# Analog2.net
KiCad netlist of a schematic drawn in Altium Designer
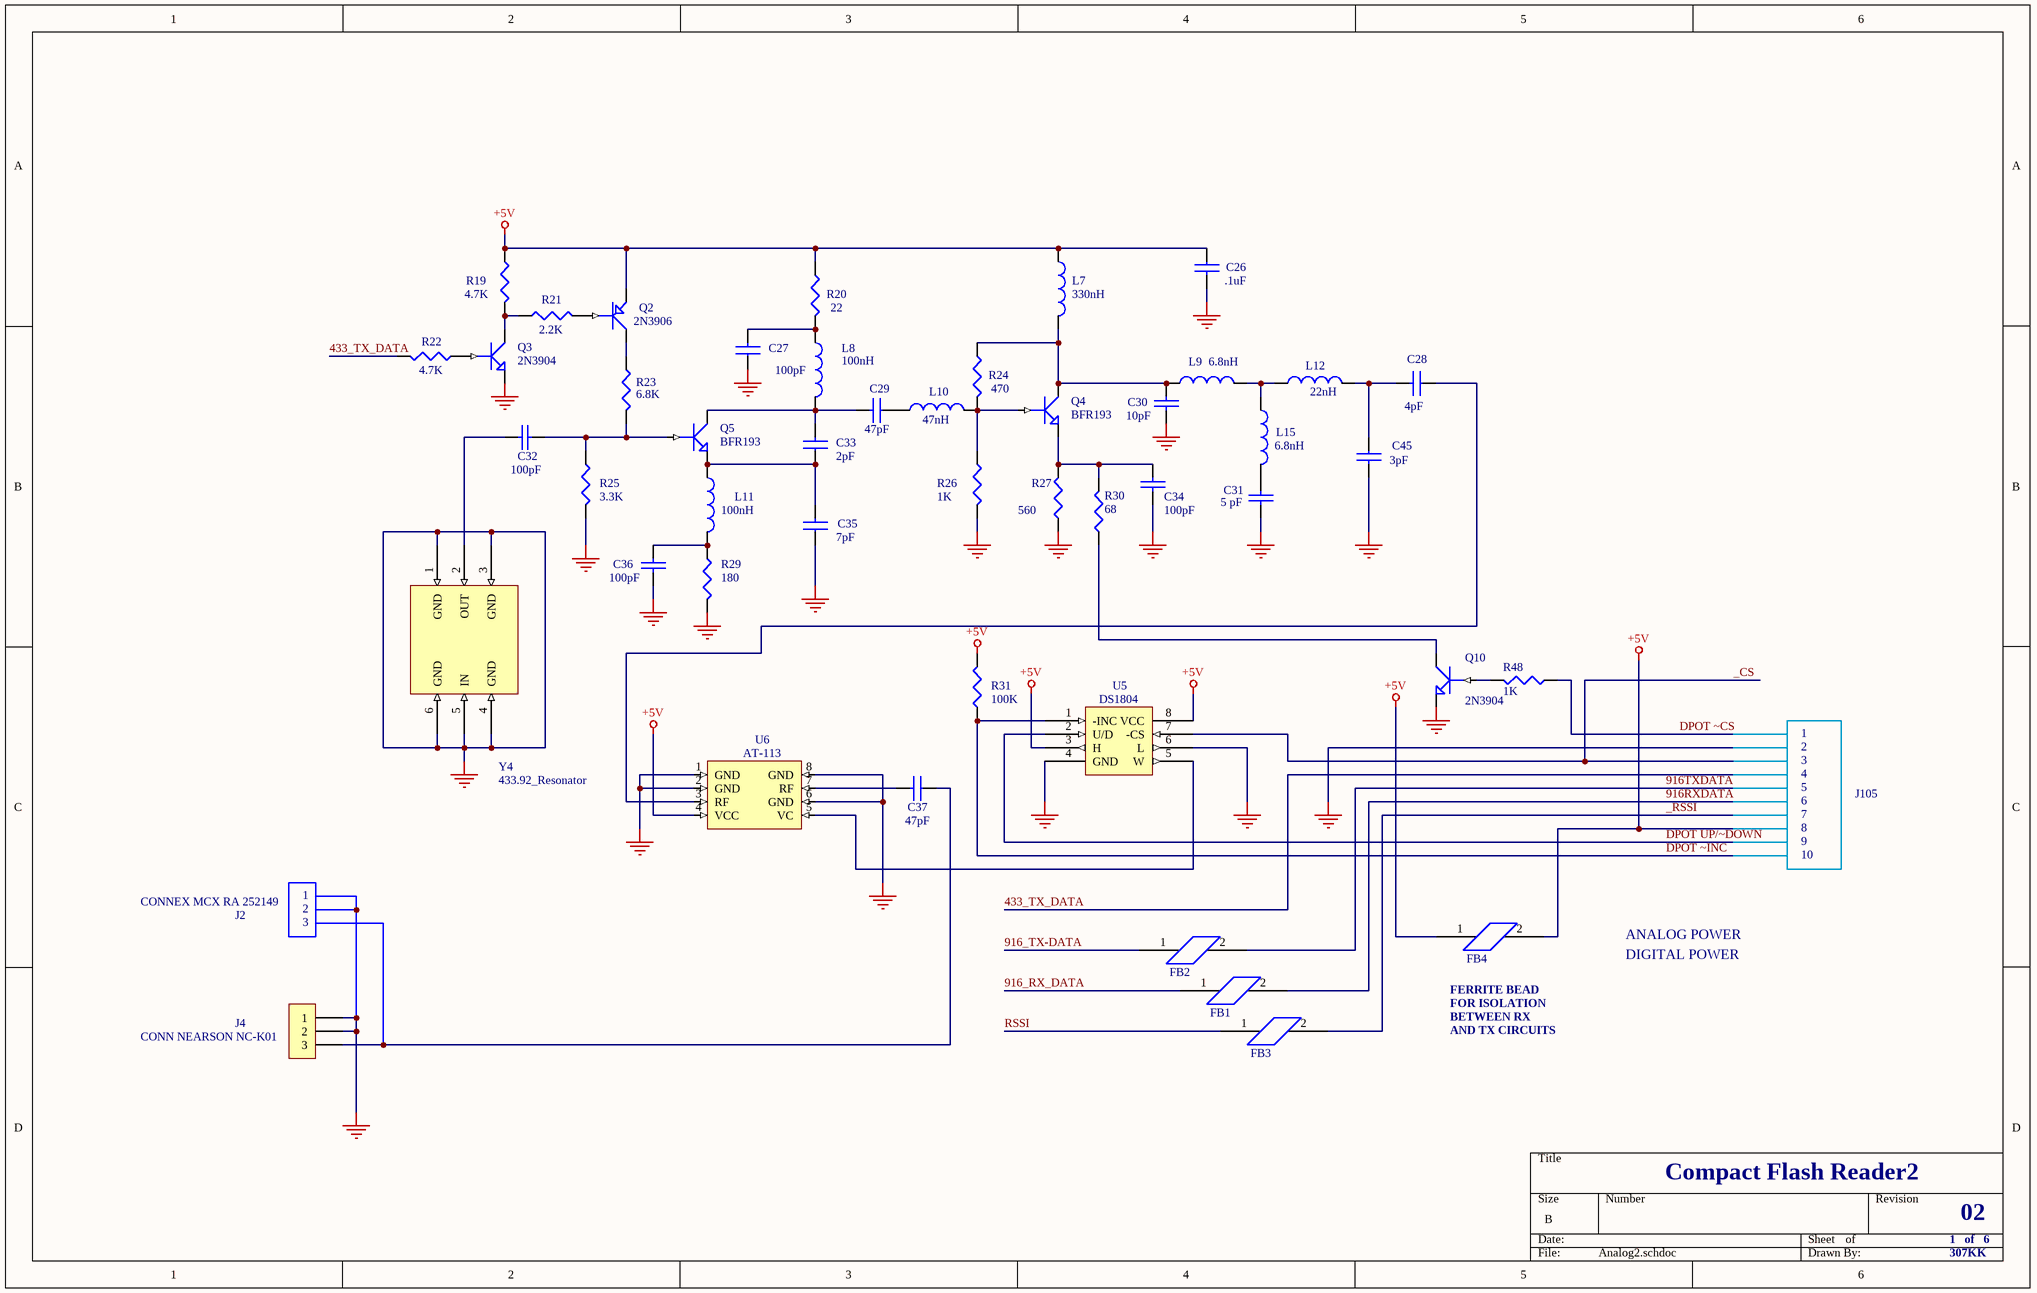
[diagram p0: Analog2.schdoc]

(export (version "E")
  (design (tool "Eeschema 10.0.6"))
  (components
    (comp (ref "C26") (value ".1uF") (footprint "0603") (libsource (lib "*") (part "CAP_NP")))
    (comp (ref "C27") (value "100pF") (footprint "0603") (libsource (lib "*") (part "CAP_NP")))
    (comp (ref "C28") (value "4pF") (footprint "0603") (libsource (lib "*") (part "CAP_NP")))
    (comp (ref "C29") (value "47pF") (footprint "0603") (libsource (lib "*") (part "CAP_NP")))
    (comp (ref "C30")
      (value "10pF")
      (footprint "0603")
      (description "Capacitor")
      (libsource (lib "*") (part "CAP"))
    )
    (comp (ref "C31")
      (value "5 pF")
      (footprint "0603")
      (description "Capacitor")
      (libsource (lib "*") (part "CAP"))
    )
    (comp (ref "C32")
      (value "100pF")
      (footprint "0603")
      (description "Capacitor")
      (libsource (lib "*") (part "CAP"))
    )
    (comp (ref "C33") (value "2pF") (footprint "0603") (libsource (lib "*") (part "CAP_NP")))
    (comp (ref "C34")
      (value "100pF")
      (footprint "0603")
      (description "Capacitor")
      (libsource (lib "*") (part "CAP"))
    )
    (comp (ref "C35") (value "7pF") (footprint "0603") (libsource (lib "*") (part "CAP_NP")))
    (comp (ref "C36")
      (value "100pF")
      (footprint "0603")
      (description "Capacitor")
      (libsource (lib "*") (part "CAP"))
    )
    (comp (ref "C37") (value "47pF") (footprint "0603") (libsource (lib "*") (part "CAP_NP")))
    (comp (ref "C45") (value "3pF") (footprint "0603") (libsource (lib "*") (part "CAP_NP")))
    (comp (ref "FB1") (value "FB") (footprint "0603") (libsource (lib "*") (part "FB_0603")))
    (comp (ref "FB2") (value "FB") (footprint "0603") (libsource (lib "*") (part "FB_0603")))
    (comp (ref "FB3") (value "FB") (footprint "0603") (libsource (lib "*") (part "FB_0603")))
    (comp (ref "FB4") (value "FB") (footprint "0603") (libsource (lib "*") (part "FB_0603")))
    (comp (ref "J4")
      (value "CONN NEARSON NC-K01")
      (footprint "CONN NEARSON NC-K01")
      (description "Connector")
      (libsource (lib "*") (part "CON3"))
    )
    (comp (ref "L7") (value "330nH") (footprint "0805") (libsource (lib "*") (part "INDUCTOR")))
    (comp (ref "L8") (value "100nH") (footprint "0603") (libsource (lib "*") (part "INDUCTOR")))
    (comp (ref "L9") (value "6.8nH") (footprint "0603") (libsource (lib "*") (part "INDUCTOR")))
    (comp (ref "L10") (value "47nH") (footprint "0603") (libsource (lib "*") (part "INDUCTOR")))
    (comp (ref "L11") (value "100nH") (footprint "0603") (libsource (lib "*") (part "INDUCTOR")))
    (comp (ref "L12") (value "22nH") (footprint "0603") (libsource (lib "*") (part "INDUCTOR")))
    (comp (ref "L15") (value "6.8nH") (footprint "0603") (libsource (lib "*") (part "INDUCTOR")))
    (comp (ref "Q2")
      (value "2N3906")
      (footprint "SOT23 TRANS")
      (description "PNP Transistor")
      (libsource (lib "*") (part "PNP1"))
    )
    (comp (ref "Q3")
      (value "2N3904")
      (footprint "SOT23 TRANS")
      (description "NPN Transistor")
      (libsource (lib "*") (part "NPN1"))
    )
    (comp (ref "Q4")
      (value "BFR193")
      (footprint "SOT23 TRANS")
      (description "NPN Transistor")
      (libsource (lib "*") (part "NPN1"))
    )
    (comp (ref "Q5")
      (value "BFR193")
      (footprint "SOT23 TRANS")
      (description "NPN Transistor")
      (libsource (lib "*") (part "NPN1"))
    )
    (comp (ref "Q10")
      (value "2N3904")
      (footprint "SOT23 TRANS")
      (description "NPN Transistor")
      (libsource (lib "*") (part "NPN1"))
    )
    (comp (ref "R19") (value "4.7K") (footprint "0603") (libsource (lib "*") (part "RESISTOR")))
    (comp (ref "R20") (value "22") (footprint "0603") (libsource (lib "*") (part "RESISTOR")))
    (comp (ref "R21") (value "2.2K") (footprint "0603") (libsource (lib "*") (part "RESISTOR")))
    (comp (ref "R22") (value "4.7K") (footprint "0603") (libsource (lib "*") (part "RESISTOR")))
    (comp (ref "R23") (value "6.8K") (footprint "0603") (libsource (lib "*") (part "RESISTOR")))
    (comp (ref "R24") (value "470") (footprint "0603") (libsource (lib "*") (part "RESISTOR")))
    (comp (ref "R25") (value "3.3K") (footprint "0603") (libsource (lib "*") (part "RESISTOR")))
    (comp (ref "R26") (value "1K") (footprint "0603") (libsource (lib "*") (part "RESISTOR")))
    (comp (ref "R27") (value "560") (footprint "0603") (libsource (lib "*") (part "RESISTOR")))
    (comp (ref "R29") (value "180") (footprint "0603") (libsource (lib "*") (part "RESISTOR")))
    (comp (ref "R30") (value "68") (footprint "0603") (libsource (lib "*") (part "RESISTOR")))
    (comp (ref "R31") (value "100K") (footprint "0603") (libsource (lib "*") (part "RESISTOR")))
    (comp (ref "R48") (value "1K") (footprint "0603") (libsource (lib "*") (part "RESISTOR")))
    (comp (ref "U5") (value "DS1804") (footprint "SO8 SMALL") (libsource (lib "*") (part "DS1804")))
    (comp (ref "U6") (value "AT-113") (footprint "SO8") (libsource (lib "*") (part "AT-113A")))
    (comp (ref "Y4")
      (value "433.92_Resonator")
      (libsource (lib "Compact Flash Reader1_1") (part "RESONATOR3"))
    )
  )
  (nets
    (net (code "1") (name "+5V") (class "Default")
      (node (ref "C26") (pin "1") (pinfunction "1_1") (pintype "passive"))
      (node (ref "FB4") (pin "1") (pinfunction "2_1") (pintype "passive"))
      (node (ref "FB4") (pin "2") (pinfunction "1_2") (pintype "passive"))
      (node (ref "L7") (pin "1") (pinfunction "1_1") (pintype "passive"))
      (node (ref "Q2") (pin "E") (pinfunction "E_E") (pintype "passive"))
      (node (ref "R19") (pin "1") (pinfunction "1_1") (pintype "passive"))
      (node (ref "R20") (pin "1") (pinfunction "1_1") (pintype "passive"))
      (node (ref "R31") (pin "1") (pinfunction "1_1") (pintype "passive"))
      (node (ref "U5") (pin "3") (pinfunction "H_3") (pintype "output"))
      (node (ref "U5") (pin "8") (pinfunction "VCC_8") (pintype "power_in"))
      (node (ref "U6") (pin "4") (pinfunction "VCC_4") (pintype "input"))
    )
    (net (code "2") (name "/433_TX_DATA") (class "Default")
      (node (ref "R22") (pin "2") (pinfunction "2_2") (pintype "passive"))
    )
    (net (code "3") (name "/916RXDATA") (class "Default")
      (node (ref "FB1") (pin "2") (pinfunction "1_2") (pintype "passive"))
    )
    (net (code "4") (name "/916TXDATA") (class "Default")
      (node (ref "FB2") (pin "2") (pinfunction "1_2") (pintype "passive"))
    )
    (net (code "5") (name "/916_RX_DATA") (class "Default")
      (node (ref "FB1") (pin "1") (pinfunction "2_1") (pintype "passive"))
    )
    (net (code "6") (name "/916_TX-DATA") (class "Default")
      (node (ref "FB2") (pin "1") (pinfunction "2_1") (pintype "passive"))
    )
    (net (code "7") (name "/DPOT UP{slash}~DOWN") (class "Default")
      (node (ref "U5") (pin "2") (pinfunction "U/D_2") (pintype "input"))
    )
    (net (code "8") (name "/DPOT ~CS") (class "Default")
      (node (ref "R48") (pin "2") (pinfunction "2_2") (pintype "passive"))
    )
    (net (code "9") (name "/DPOT ~INC") (class "Default")
      (node (ref "R31") (pin "2") (pinfunction "2_2") (pintype "passive"))
      (node (ref "U5") (pin "1") (pinfunction "-INC_1") (pintype "input"))
    )
    (net (code "10") (name "/RSSI") (class "Default")
      (node (ref "FB3") (pin "1") (pinfunction "2_1") (pintype "passive"))
    )
    (net (code "11") (name "/_CS") (class "Default")
      (node (ref "U5") (pin "7") (pinfunction "-CS_7") (pintype "input"))
    )
    (net (code "12") (name "/_RSSI") (class "Default")
      (node (ref "FB3") (pin "2") (pinfunction "1_2") (pintype "passive"))
    )
    (net (code "13") (name "GND_SIGNAL") (class "Default")
      (node (ref "C26") (pin "2") (pinfunction "2_2") (pintype "passive"))
      (node (ref "C27") (pin "1") (pinfunction "1_1") (pintype "passive"))
      (node (ref "C30") (pin "2") (pinfunction "2_2") (pintype "passive"))
      (node (ref "C31") (pin "2") (pinfunction "2_2") (pintype "passive"))
      (node (ref "C34") (pin "2") (pinfunction "2_2") (pintype "passive"))
      (node (ref "C35") (pin "1") (pinfunction "1_1") (pintype "passive"))
      (node (ref "C36") (pin "2") (pinfunction "2_2") (pintype "passive"))
      (node (ref "C45") (pin "2") (pinfunction "2_2") (pintype "passive"))
      (node (ref "J4") (pin "1") (pinfunction "1_1") (pintype "passive"))
      (node (ref "J4") (pin "2") (pinfunction "2_2") (pintype "passive"))
      (node (ref "Q10") (pin "E") (pinfunction "E_E") (pintype "passive"))
      (node (ref "Q3") (pin "E") (pinfunction "E_E") (pintype "passive"))
      (node (ref "R25") (pin "2") (pinfunction "2_2") (pintype "passive"))
      (node (ref "R26") (pin "2") (pinfunction "2_2") (pintype "passive"))
      (node (ref "R27") (pin "2") (pinfunction "2_2") (pintype "passive"))
      (node (ref "R29") (pin "2") (pinfunction "2_2") (pintype "passive"))
      (node (ref "U5") (pin "4") (pinfunction "GND_4") (pintype "power_in"))
      (node (ref "U5") (pin "6") (pinfunction "L_6") (pintype "output"))
      (node (ref "U6") (pin "1") (pinfunction "GND_1") (pintype "input"))
      (node (ref "U6") (pin "2") (pinfunction "GND_2") (pintype "input"))
      (node (ref "U6") (pin "6") (pinfunction "GND_6") (pintype "input"))
      (node (ref "U6") (pin "8") (pinfunction "GND_8") (pintype "input"))
      (node (ref "Y4") (pin "1") (pinfunction "GND_1") (pintype "input"))
      (node (ref "Y4") (pin "3") (pinfunction "GND_3") (pintype "input"))
      (node (ref "Y4") (pin "4") (pinfunction "GND_4") (pintype "input"))
      (node (ref "Y4") (pin "5") (pinfunction "IN_5") (pintype "input"))
      (node (ref "Y4") (pin "6") (pinfunction "GND_6") (pintype "input"))
    )
    (net (code "14") (name "Net-(C27-Pad2)") (class "Default")
      (node (ref "C27") (pin "2") (pinfunction "2_2") (pintype "passive"))
      (node (ref "L8") (pin "1") (pinfunction "1_1") (pintype "passive"))
      (node (ref "R20") (pin "2") (pinfunction "2_2") (pintype "passive"))
    )
    (net (code "15") (name "Net-(C28-Pad1)") (class "Default")
      (node (ref "C28") (pin "1") (pinfunction "1_1") (pintype "passive"))
      (node (ref "U6") (pin "3") (pinfunction "RF_3") (pintype "input"))
    )
    (net (code "16") (name "Net-(C28-Pad2)") (class "Default")
      (node (ref "C28") (pin "2") (pinfunction "2_2") (pintype "passive"))
      (node (ref "C45") (pin "1") (pinfunction "1_1") (pintype "passive"))
      (node (ref "L12") (pin "2") (pinfunction "2_2") (pintype "passive"))
    )
    (net (code "17") (name "Net-(C29-Pad1)") (class "Default")
      (node (ref "C29") (pin "1") (pinfunction "1_1") (pintype "passive"))
      (node (ref "L10") (pin "1") (pinfunction "1_1") (pintype "passive"))
    )
    (net (code "18") (name "Net-(C29-Pad2)") (class "Default")
      (node (ref "C29") (pin "2") (pinfunction "2_2") (pintype "passive"))
      (node (ref "C33") (pin "2") (pinfunction "2_2") (pintype "passive"))
      (node (ref "L8") (pin "2") (pinfunction "2_2") (pintype "passive"))
      (node (ref "Q5") (pin "C") (pinfunction "C_C") (pintype "passive"))
    )
    (net (code "19") (name "Net-(C30-Pad1)") (class "Default")
      (node (ref "C30") (pin "1") (pinfunction "1_1") (pintype "passive"))
      (node (ref "L7") (pin "2") (pinfunction "2_2") (pintype "passive"))
      (node (ref "L9") (pin "1") (pinfunction "1_1") (pintype "passive"))
      (node (ref "Q4") (pin "C") (pinfunction "C_C") (pintype "passive"))
      (node (ref "R24") (pin "1") (pinfunction "1_1") (pintype "passive"))
    )
    (net (code "20") (name "Net-(C31-Pad1)") (class "Default")
      (node (ref "C31") (pin "1") (pinfunction "1_1") (pintype "passive"))
      (node (ref "L15") (pin "2") (pinfunction "2_2") (pintype "passive"))
    )
    (net (code "21") (name "Net-(C32-Pad2)") (class "Default")
      (node (ref "C32") (pin "2") (pinfunction "2_2") (pintype "passive"))
      (node (ref "Q5") (pin "B") (pinfunction "B_B") (pintype "input"))
      (node (ref "R23") (pin "2") (pinfunction "2_2") (pintype "passive"))
      (node (ref "R25") (pin "1") (pinfunction "1_1") (pintype "passive"))
    )
    (net (code "22") (name "Net-(C33-Pad1)") (class "Default")
      (node (ref "C33") (pin "1") (pinfunction "1_1") (pintype "passive"))
      (node (ref "C35") (pin "2") (pinfunction "2_2") (pintype "passive"))
      (node (ref "L11") (pin "1") (pinfunction "1_1") (pintype "passive"))
      (node (ref "Q5") (pin "E") (pinfunction "E_E") (pintype "passive"))
    )
    (net (code "23") (name "Net-(C34-Pad1)") (class "Default")
      (node (ref "C34") (pin "1") (pinfunction "1_1") (pintype "passive"))
      (node (ref "Q4") (pin "E") (pinfunction "E_E") (pintype "passive"))
      (node (ref "R27") (pin "1") (pinfunction "1_1") (pintype "passive"))
      (node (ref "R30") (pin "2") (pinfunction "2_2") (pintype "passive"))
    )
    (net (code "24") (name "Net-(C36-Pad1)") (class "Default")
      (node (ref "C36") (pin "1") (pinfunction "1_1") (pintype "passive"))
      (node (ref "L11") (pin "2") (pinfunction "2_2") (pintype "passive"))
      (node (ref "R29") (pin "1") (pinfunction "1_1") (pintype "passive"))
    )
    (net (code "25") (name "Net-(C37-Pad1)") (class "Default")
      (node (ref "C37") (pin "1") (pinfunction "1_1") (pintype "passive"))
      (node (ref "J4") (pin "3") (pinfunction "3_3") (pintype "passive"))
    )
    (net (code "26") (name "Net-(C37-Pad2)") (class "Default")
      (node (ref "C37") (pin "2") (pinfunction "2_2") (pintype "passive"))
      (node (ref "U6") (pin "7") (pinfunction "RF_7") (pintype "input"))
    )
    (net (code "27") (name "Net-(L10-Pad2)") (class "Default")
      (node (ref "L10") (pin "2") (pinfunction "2_2") (pintype "passive"))
      (node (ref "Q4") (pin "B") (pinfunction "B_B") (pintype "input"))
      (node (ref "R24") (pin "2") (pinfunction "2_2") (pintype "passive"))
      (node (ref "R26") (pin "1") (pinfunction "1_1") (pintype "passive"))
    )
    (net (code "28") (name "Net-(L12-Pad1)") (class "Default")
      (node (ref "L12") (pin "1") (pinfunction "1_1") (pintype "passive"))
      (node (ref "L15") (pin "1") (pinfunction "1_1") (pintype "passive"))
      (node (ref "L9") (pin "2") (pinfunction "2_2") (pintype "passive"))
    )
    (net (code "29") (name "Net-(Q2-PadB)") (class "Default")
      (node (ref "Q2") (pin "B") (pinfunction "B_B") (pintype "input"))
      (node (ref "R21") (pin "2") (pinfunction "2_2") (pintype "passive"))
    )
    (net (code "30") (name "Net-(Q2-PadC)") (class "Default")
      (node (ref "Q2") (pin "C") (pinfunction "C_C") (pintype "passive"))
      (node (ref "R23") (pin "1") (pinfunction "1_1") (pintype "passive"))
    )
    (net (code "31") (name "Net-(Q3-PadB)") (class "Default")
      (node (ref "Q3") (pin "B") (pinfunction "B_B") (pintype "input"))
      (node (ref "R22") (pin "1") (pinfunction "1_1") (pintype "passive"))
    )
    (net (code "32") (name "Net-(Q3-PadC)") (class "Default")
      (node (ref "Q3") (pin "C") (pinfunction "C_C") (pintype "passive"))
      (node (ref "R19") (pin "2") (pinfunction "2_2") (pintype "passive"))
      (node (ref "R21") (pin "1") (pinfunction "1_1") (pintype "passive"))
    )
    (net (code "33") (name "Net-(Q10-PadB)") (class "Default")
      (node (ref "Q10") (pin "B") (pinfunction "B_B") (pintype "input"))
      (node (ref "R48") (pin "1") (pinfunction "1_1") (pintype "passive"))
    )
    (net (code "34") (name "Net-(Q10-PadC)") (class "Default")
      (node (ref "Q10") (pin "C") (pinfunction "C_C") (pintype "passive"))
      (node (ref "R30") (pin "1") (pinfunction "1_1") (pintype "passive"))
    )
    (net (code "35") (name "Net-(U5-W)") (class "Default")
      (node (ref "U5") (pin "5") (pinfunction "W_5") (pintype "output"))
      (node (ref "U6") (pin "5") (pinfunction "VC_5") (pintype "input"))
    )
    (net (code "36") (name "Net-(Y4-OUT)") (class "Default")
      (node (ref "C32") (pin "1") (pinfunction "1_1") (pintype "passive"))
      (node (ref "Y4") (pin "2") (pinfunction "OUT_2") (pintype "input"))
    )
  )
)
